# ActuatorMKII_Microcontroller.net
KiCad netlist of a schematic drawn in Altium Designer
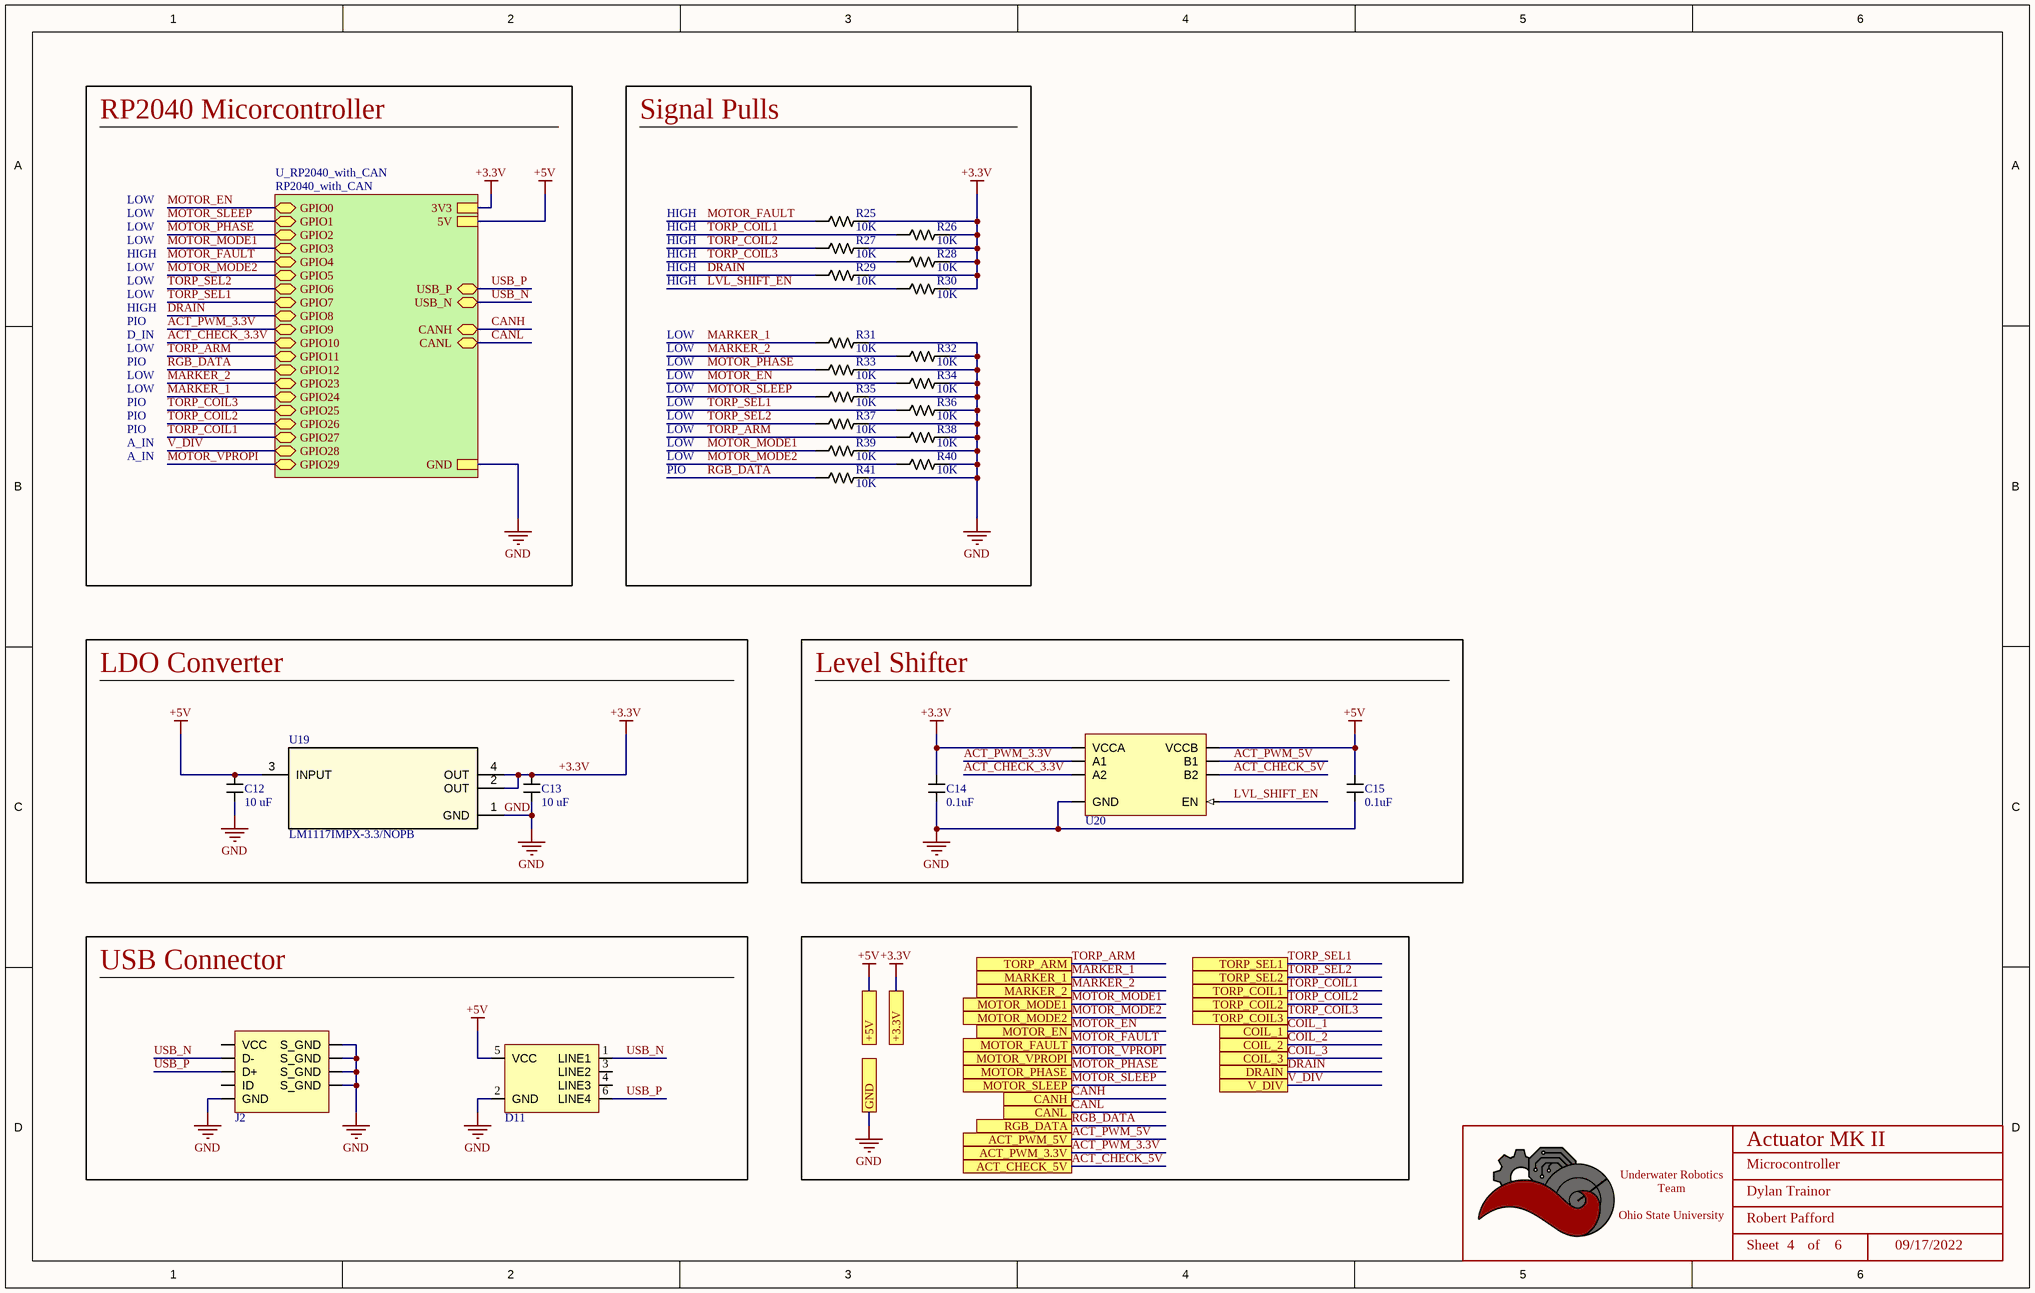
[diagram p0: ActuatorMKII_Microcontroller.SchDoc]

(export (version "E")
  (design (tool "Eeschema 10.0.6"))
  (components
    (comp (ref "C12")
      (value "10uF Ceramic 6.3V")
      (footprint "CAPACITOR_0603")
      (description "Cap 10uF 6.3V +/-20%\r\nCeramic 0603")
      (fields
        (field (name "TOLERANCE") "+/- 20%")
        (field (name "VOLTAGE") "6.3V")
        (field (name "VALUE (UF)") "10 uF")
        (field (name "MADE BY") "Flip B")
      )
      (libsource (lib "Capacitors") (part "CAPACITOR_10uF_0603"))
    )
    (comp (ref "C13")
      (value "10uF Ceramic 6.3V")
      (footprint "CAPACITOR_0603")
      (description "Cap 10uF 6.3V +/-20%\r\nCeramic 0603")
      (fields
        (field (name "TOLERANCE") "+/- 20%")
        (field (name "VOLTAGE") "6.3V")
        (field (name "VALUE (UF)") "10 uF")
        (field (name "MADE BY") "Flip B")
      )
      (libsource (lib "Capacitors") (part "CAPACITOR_10uF_0603"))
    )
    (comp (ref "C14")
      (value "0.1uF")
      (footprint "CAPACITOR_0603")
      (description "Cap 100nF 6.3V +/-10%\r\nCeramic 0603")
      (fields
        (field (name "TOLERANCE") "+/- 10%")
        (field (name "VOLTAGE") "6.3V")
        (field (name "MADE BY") "Flip B")
      )
      (libsource (lib "Capacitors") (part "CAPACITOR_0.1uF_0603"))
    )
    (comp (ref "C15")
      (value "0.1uF")
      (footprint "CAPACITOR_0603")
      (description "Cap 100nF 6.3V +/-10%\r\nCeramic 0603")
      (fields
        (field (name "TOLERANCE") "+/- 10%")
        (field (name "VOLTAGE") "6.3V")
        (field (name "MADE BY") "Flip B")
      )
      (libsource (lib "Capacitors") (part "CAPACITOR_0.1uF_0603"))
    )
    (comp (ref "D11")
      (value "TVS DIODE 5VWM 25VC SOT23-6")
      (footprint "SOT 23-6L")
      (description "25V Clamp 6A (8/20µs) Ipp Tvs Diode Surface Mount SOT-23-6")
      (fields (field (name "MADE BY") "Robert Pafford"))
      (libsource (lib "Diodes") (part "RCLAMP0504S.TCT"))
    )
    (comp (ref "J2")
      (value "USB_MICRO R/A")
      (footprint "CONN_MINIUSB")
      (description "Amphenol Micro USB-B\r\nUSB2.0 5 Pin Right Angle SMD")
      (fields (field (name "MANUFACTURER") "Amphenol") (field (name "CREATED BY") "Flip B"))
      (libsource (lib "Connectors") (part "CONN_MICROUSB"))
    )
    (comp (ref "R25")
      (value "10k Ohm 5% 1/10W")
      (footprint "RESISTOR_0603")
      (description "RES 10k OHM 5% 1/10W 0603")
      (fields
        (field (name "TOLERANCE") "+/- 5%")
        (field (name "VALUE  (OHMS)") "10K")
        (field (name "MADE BY") "Robert Pafford")
      )
      (libsource (lib "Resistors") (part "RESISTOR_10K_0603"))
    )
    (comp (ref "R26")
      (value "10k Ohm 5% 1/10W")
      (footprint "RESISTOR_0603")
      (description "RES 10k OHM 5% 1/10W 0603")
      (fields
        (field (name "TOLERANCE") "+/- 5%")
        (field (name "VALUE  (OHMS)") "10K")
        (field (name "MADE BY") "Robert Pafford")
      )
      (libsource (lib "Resistors") (part "RESISTOR_10K_0603"))
    )
    (comp (ref "R27")
      (value "10k Ohm 5% 1/10W")
      (footprint "RESISTOR_0603")
      (description "RES 10k OHM 5% 1/10W 0603")
      (fields
        (field (name "TOLERANCE") "+/- 5%")
        (field (name "VALUE  (OHMS)") "10K")
        (field (name "MADE BY") "Robert Pafford")
      )
      (libsource (lib "Resistors") (part "RESISTOR_10K_0603"))
    )
    (comp (ref "R28")
      (value "10k Ohm 5% 1/10W")
      (footprint "RESISTOR_0603")
      (description "RES 10k OHM 5% 1/10W 0603")
      (fields
        (field (name "TOLERANCE") "+/- 5%")
        (field (name "VALUE  (OHMS)") "10K")
        (field (name "MADE BY") "Robert Pafford")
      )
      (libsource (lib "Resistors") (part "RESISTOR_10K_0603"))
    )
    (comp (ref "R29")
      (value "10k Ohm 5% 1/10W")
      (footprint "RESISTOR_0603")
      (description "RES 10k OHM 5% 1/10W 0603")
      (fields
        (field (name "TOLERANCE") "+/- 5%")
        (field (name "VALUE  (OHMS)") "10K")
        (field (name "MADE BY") "Robert Pafford")
      )
      (libsource (lib "Resistors") (part "RESISTOR_10K_0603"))
    )
    (comp (ref "R30")
      (value "10k Ohm 5% 1/10W")
      (footprint "RESISTOR_0603")
      (description "RES 10k OHM 5% 1/10W 0603")
      (fields
        (field (name "TOLERANCE") "+/- 5%")
        (field (name "VALUE  (OHMS)") "10K")
        (field (name "MADE BY") "Robert Pafford")
      )
      (libsource (lib "Resistors") (part "RESISTOR_10K_0603"))
    )
    (comp (ref "R31")
      (value "10k Ohm 5% 1/10W")
      (footprint "RESISTOR_0603")
      (description "RES 10k OHM 5% 1/10W 0603")
      (fields
        (field (name "TOLERANCE") "+/- 5%")
        (field (name "VALUE  (OHMS)") "10K")
        (field (name "MADE BY") "Robert Pafford")
      )
      (libsource (lib "Resistors") (part "RESISTOR_10K_0603"))
    )
    (comp (ref "R32")
      (value "10k Ohm 5% 1/10W")
      (footprint "RESISTOR_0603")
      (description "RES 10k OHM 5% 1/10W 0603")
      (fields
        (field (name "TOLERANCE") "+/- 5%")
        (field (name "VALUE  (OHMS)") "10K")
        (field (name "MADE BY") "Robert Pafford")
      )
      (libsource (lib "Resistors") (part "RESISTOR_10K_0603"))
    )
    (comp (ref "R33")
      (value "10k Ohm 5% 1/10W")
      (footprint "RESISTOR_0603")
      (description "RES 10k OHM 5% 1/10W 0603")
      (fields
        (field (name "TOLERANCE") "+/- 5%")
        (field (name "VALUE  (OHMS)") "10K")
        (field (name "MADE BY") "Robert Pafford")
      )
      (libsource (lib "Resistors") (part "RESISTOR_10K_0603"))
    )
    (comp (ref "R34")
      (value "10k Ohm 5% 1/10W")
      (footprint "RESISTOR_0603")
      (description "RES 10k OHM 5% 1/10W 0603")
      (fields
        (field (name "TOLERANCE") "+/- 5%")
        (field (name "VALUE  (OHMS)") "10K")
        (field (name "MADE BY") "Robert Pafford")
      )
      (libsource (lib "Resistors") (part "RESISTOR_10K_0603"))
    )
    (comp (ref "R35")
      (value "10k Ohm 5% 1/10W")
      (footprint "RESISTOR_0603")
      (description "RES 10k OHM 5% 1/10W 0603")
      (fields
        (field (name "TOLERANCE") "+/- 5%")
        (field (name "VALUE  (OHMS)") "10K")
        (field (name "MADE BY") "Robert Pafford")
      )
      (libsource (lib "Resistors") (part "RESISTOR_10K_0603"))
    )
    (comp (ref "R36")
      (value "10k Ohm 5% 1/10W")
      (footprint "RESISTOR_0603")
      (description "RES 10k OHM 5% 1/10W 0603")
      (fields
        (field (name "TOLERANCE") "+/- 5%")
        (field (name "VALUE  (OHMS)") "10K")
        (field (name "MADE BY") "Robert Pafford")
      )
      (libsource (lib "Resistors") (part "RESISTOR_10K_0603"))
    )
    (comp (ref "R37")
      (value "10k Ohm 5% 1/10W")
      (footprint "RESISTOR_0603")
      (description "RES 10k OHM 5% 1/10W 0603")
      (fields
        (field (name "TOLERANCE") "+/- 5%")
        (field (name "VALUE  (OHMS)") "10K")
        (field (name "MADE BY") "Robert Pafford")
      )
      (libsource (lib "Resistors") (part "RESISTOR_10K_0603"))
    )
    (comp (ref "R38")
      (value "10k Ohm 5% 1/10W")
      (footprint "RESISTOR_0603")
      (description "RES 10k OHM 5% 1/10W 0603")
      (fields
        (field (name "TOLERANCE") "+/- 5%")
        (field (name "VALUE  (OHMS)") "10K")
        (field (name "MADE BY") "Robert Pafford")
      )
      (libsource (lib "Resistors") (part "RESISTOR_10K_0603"))
    )
    (comp (ref "R39")
      (value "10k Ohm 5% 1/10W")
      (footprint "RESISTOR_0603")
      (description "RES 10k OHM 5% 1/10W 0603")
      (fields
        (field (name "TOLERANCE") "+/- 5%")
        (field (name "VALUE  (OHMS)") "10K")
        (field (name "MADE BY") "Robert Pafford")
      )
      (libsource (lib "Resistors") (part "RESISTOR_10K_0603"))
    )
    (comp (ref "R40")
      (value "10k Ohm 5% 1/10W")
      (footprint "RESISTOR_0603")
      (description "RES 10k OHM 5% 1/10W 0603")
      (fields
        (field (name "TOLERANCE") "+/- 5%")
        (field (name "VALUE  (OHMS)") "10K")
        (field (name "MADE BY") "Robert Pafford")
      )
      (libsource (lib "Resistors") (part "RESISTOR_10K_0603"))
    )
    (comp (ref "R41")
      (value "10k Ohm 5% 1/10W")
      (footprint "RESISTOR_0603")
      (description "RES 10k OHM 5% 1/10W 0603")
      (fields
        (field (name "TOLERANCE") "+/- 5%")
        (field (name "VALUE  (OHMS)") "10K")
        (field (name "MADE BY") "Robert Pafford")
      )
      (libsource (lib "Resistors") (part "RESISTOR_10K_0603"))
    )
    (comp (ref "U19")
      (value "LM1117IMPX-3.3/NOPB")
      (footprint "SOT-223-4")
      (description "IC REG LIN 3.3V 800MA SOT223-4")
      (fields
        (field (name "PARTNUMBER") "LM1117IMP-3.3/NOPB")
        (field (name "MANUFACTURER") "Texas Instruments")
        (field (name "CREATED BY") "Dylan T")
      )
      (libsource (lib "Converter") (part "LM1117IMPX-3.3/NOPB"))
    )
    (comp (ref "U20")
      (value "IC TRANSLTR BIDIRECTIONAL 8MSOP")
      (footprint "MSOP-8_PI4ULS5V202UEX")
      (description "Voltage Level Translator Bidirectional 1 Circuit 2 Channel 20Mbps 8-MSOP")
      (fields (field (name "MADE BY") "Robert Pafford"))
      (libsource (lib "Integrated Circuits") (part "PI4ULS5V202UEX"))
    )
  )
  (nets
    (net (code "1") (name "+3.3V") (class "Default")
      (node (ref "C13") (pin "1") (pinfunction "1_1") (pintype "passive"))
      (node (ref "C14") (pin "1") (pinfunction "1_1") (pintype "passive"))
      (node (ref "R25") (pin "1") (pinfunction "1_1") (pintype "passive"))
      (node (ref "R26") (pin "1") (pinfunction "1_1") (pintype "passive"))
      (node (ref "R27") (pin "1") (pinfunction "1_1") (pintype "passive"))
      (node (ref "R28") (pin "1") (pinfunction "1_1") (pintype "passive"))
      (node (ref "R29") (pin "1") (pinfunction "1_1") (pintype "passive"))
      (node (ref "R30") (pin "1") (pinfunction "1_1") (pintype "passive"))
      (node (ref "U19") (pin "2") (pinfunction "OUT_2") (pintype "power_in"))
      (node (ref "U19") (pin "4") (pinfunction "OUT_4") (pintype "power_in"))
      (node (ref "U20") (pin "1") (pinfunction "VCCA_1") (pintype "power_in"))
    )
    (net (code "2") (name "+5V") (class "Default")
      (node (ref "C12") (pin "1") (pinfunction "1_1") (pintype "passive"))
      (node (ref "C15") (pin "1") (pinfunction "1_1") (pintype "passive"))
      (node (ref "D11") (pin "5") (pinfunction "VCC_5") (pintype "power_in"))
      (node (ref "U19") (pin "3") (pinfunction "INPUT_3") (pintype "power_in"))
      (node (ref "U20") (pin "8") (pinfunction "VCCB_8") (pintype "power_in"))
    )
    (net (code "3") (name "/ACT_CHECK_3.3V") (class "Default")
      (node (ref "U20") (pin "3") (pinfunction "A2_3") (pintype "bidirectional"))
    )
    (net (code "4") (name "/ACT_CHECK_5V") (class "Default")
      (node (ref "U20") (pin "6") (pinfunction "B2_6") (pintype "bidirectional"))
    )
    (net (code "5") (name "/ACT_PWM_3.3V") (class "Default")
      (node (ref "U20") (pin "2") (pinfunction "A1_2") (pintype "bidirectional"))
    )
    (net (code "6") (name "/ACT_PWM_5V") (class "Default")
      (node (ref "U20") (pin "7") (pinfunction "B1_7") (pintype "bidirectional"))
    )
    (net (code "12") (name "/DRAIN") (class "Default")
      (node (ref "R29") (pin "2") (pinfunction "2_2") (pintype "passive"))
    )
    (net (code "13") (name "/LVL_SHIFT_EN") (class "Default")
      (node (ref "R30") (pin "2") (pinfunction "2_2") (pintype "passive"))
      (node (ref "U20") (pin "5") (pinfunction "EN_5") (pintype "input"))
    )
    (net (code "14") (name "/MARKER_1") (class "Default")
      (node (ref "R31") (pin "2") (pinfunction "2_2") (pintype "passive"))
    )
    (net (code "15") (name "/MARKER_2") (class "Default")
      (node (ref "R32") (pin "2") (pinfunction "2_2") (pintype "passive"))
    )
    (net (code "16") (name "/MOTOR_EN") (class "Default")
      (node (ref "R34") (pin "2") (pinfunction "2_2") (pintype "passive"))
    )
    (net (code "17") (name "/MOTOR_FAULT") (class "Default")
      (node (ref "R25") (pin "2") (pinfunction "2_2") (pintype "passive"))
    )
    (net (code "18") (name "/MOTOR_MODE1") (class "Default")
      (node (ref "R39") (pin "2") (pinfunction "2_2") (pintype "passive"))
    )
    (net (code "19") (name "/MOTOR_MODE2") (class "Default")
      (node (ref "R40") (pin "2") (pinfunction "2_2") (pintype "passive"))
    )
    (net (code "20") (name "/MOTOR_PHASE") (class "Default")
      (node (ref "R33") (pin "2") (pinfunction "2_2") (pintype "passive"))
    )
    (net (code "21") (name "/MOTOR_SLEEP") (class "Default")
      (node (ref "R35") (pin "2") (pinfunction "2_2") (pintype "passive"))
    )
    (net (code "23") (name "/RGB_DATA") (class "Default")
      (node (ref "R41") (pin "2") (pinfunction "2_2") (pintype "passive"))
    )
    (net (code "24") (name "/TORP_ARM") (class "Default")
      (node (ref "R38") (pin "2") (pinfunction "2_2") (pintype "passive"))
    )
    (net (code "25") (name "/TORP_COIL1") (class "Default")
      (node (ref "R26") (pin "2") (pinfunction "2_2") (pintype "passive"))
    )
    (net (code "26") (name "/TORP_COIL2") (class "Default")
      (node (ref "R27") (pin "2") (pinfunction "2_2") (pintype "passive"))
    )
    (net (code "27") (name "/TORP_COIL3") (class "Default")
      (node (ref "R28") (pin "2") (pinfunction "2_2") (pintype "passive"))
    )
    (net (code "28") (name "/TORP_SEL1") (class "Default")
      (node (ref "R36") (pin "2") (pinfunction "2_2") (pintype "passive"))
    )
    (net (code "29") (name "/TORP_SEL2") (class "Default")
      (node (ref "R37") (pin "2") (pinfunction "2_2") (pintype "passive"))
    )
    (net (code "30") (name "/USB_N") (class "Default")
      (node (ref "D11") (pin "1") (pinfunction "LINE1_1") (pintype "passive"))
      (node (ref "J2") (pin "2") (pinfunction "D-_2") (pintype "passive"))
    )
    (net (code "31") (name "/USB_P") (class "Default")
      (node (ref "D11") (pin "6") (pinfunction "LINE4_6") (pintype "passive"))
      (node (ref "J2") (pin "3") (pinfunction "D+_3") (pintype "passive"))
    )
    (net (code "33") (name "GND") (class "Default")
      (node (ref "C12") (pin "2") (pinfunction "2_2") (pintype "passive"))
      (node (ref "C13") (pin "2") (pinfunction "2_2") (pintype "passive"))
      (node (ref "C14") (pin "2") (pinfunction "2_2") (pintype "passive"))
      (node (ref "C15") (pin "2") (pinfunction "2_2") (pintype "passive"))
      (node (ref "D11") (pin "2") (pinfunction "GND_2") (pintype "power_in"))
      (node (ref "J2") (pin "5") (pinfunction "GND_5") (pintype "passive"))
      (node (ref "J2") (pin "6") (pinfunction "S_GND_6") (pintype "passive"))
      (node (ref "J2") (pin "7") (pinfunction "S_GND_7") (pintype "passive"))
      (node (ref "J2") (pin "8") (pinfunction "S_GND_8") (pintype "passive"))
      (node (ref "J2") (pin "9") (pinfunction "S_GND_9") (pintype "passive"))
      (node (ref "R31") (pin "1") (pinfunction "1_1") (pintype "passive"))
      (node (ref "R32") (pin "1") (pinfunction "1_1") (pintype "passive"))
      (node (ref "R33") (pin "1") (pinfunction "1_1") (pintype "passive"))
      (node (ref "R34") (pin "1") (pinfunction "1_1") (pintype "passive"))
      (node (ref "R35") (pin "1") (pinfunction "1_1") (pintype "passive"))
      (node (ref "R36") (pin "1") (pinfunction "1_1") (pintype "passive"))
      (node (ref "R37") (pin "1") (pinfunction "1_1") (pintype "passive"))
      (node (ref "R38") (pin "1") (pinfunction "1_1") (pintype "passive"))
      (node (ref "R39") (pin "1") (pinfunction "1_1") (pintype "passive"))
      (node (ref "R40") (pin "1") (pinfunction "1_1") (pintype "passive"))
      (node (ref "R41") (pin "1") (pinfunction "1_1") (pintype "passive"))
      (node (ref "U19") (pin "1") (pinfunction "GND_1") (pintype "power_in"))
      (node (ref "U20") (pin "4") (pinfunction "GND_4") (pintype "power_in"))
    )
    (net (code "34") (name "unconnected-(D11-LINE2-Pad3)") (class "Default")
      (node (ref "D11") (pin "3") (pinfunction "LINE2_3") (pintype "passive"))
    )
    (net (code "35") (name "unconnected-(D11-LINE3-Pad4)") (class "Default")
      (node (ref "D11") (pin "4") (pinfunction "LINE3_4") (pintype "passive"))
    )
    (net (code "36") (name "unconnected-(J2-ID-Pad4)") (class "Default")
      (node (ref "J2") (pin "4") (pinfunction "ID_4") (pintype "passive"))
    )
    (net (code "37") (name "unconnected-(J2-VCC-Pad1)") (class "Default")
      (node (ref "J2") (pin "1") (pinfunction "VCC_1") (pintype "passive"))
    )
  )
)
